# w13-input.net
KiCad netlist of a schematic drawn in EAGLE
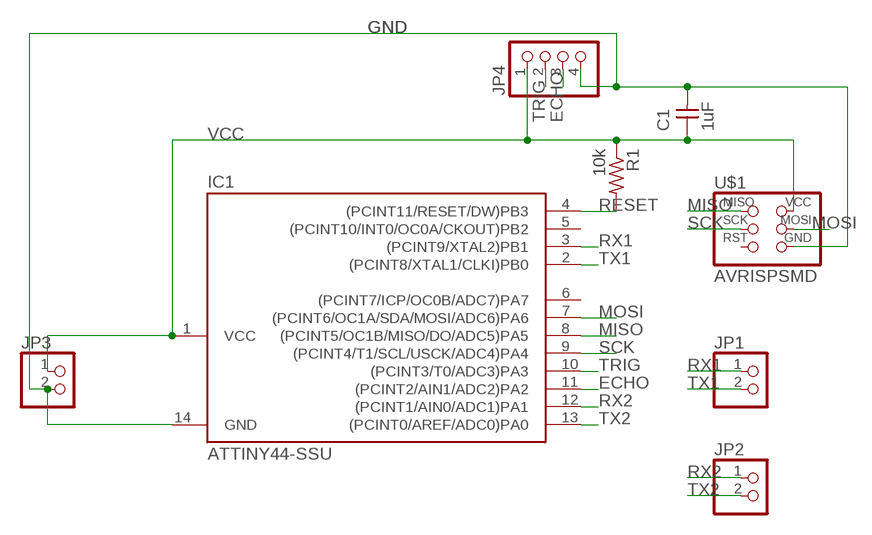
[diagram p0: schematic, sheet 1]

(export (version "E")
  (design (tool "Eeschema 10.0.6"))
  (components
    (comp (ref "C1")
      (value "1uF")
      (footprint "eagle-import:C1206FAB")
      (libsource (lib "eagle-import") (part "CAP-UNPOLARIZEDFAB"))
    )
    (comp (ref "IC1")
      (value "ATTINY44-SSU")
      (footprint "eagle-import:SOIC14")
      (libsource (lib "eagle-import") (part "ATTINY44-SSU"))
    )
    (comp (ref "JP1")
      (value "PINHD-1X2")
      (footprint "eagle-import:1X02")
      (libsource (lib "eagle-import") (part "PINHD-1X2"))
    )
    (comp (ref "JP2")
      (value "PINHD-1X2")
      (footprint "eagle-import:1X02")
      (libsource (lib "eagle-import") (part "PINHD-1X2"))
    )
    (comp (ref "JP3")
      (value "PINHD-1X2")
      (footprint "eagle-import:1X02")
      (libsource (lib "eagle-import") (part "PINHD-1X2"))
    )
    (comp (ref "JP4")
      (value "PINHD-1X4")
      (footprint "eagle-import:1X04")
      (libsource (lib "eagle-import") (part "PINHD-1X4"))
    )
    (comp (ref "R1")
      (value "10k")
      (footprint "eagle-import:R1206FAB")
      (libsource (lib "eagle-import") (part "RES-US1206FAB"))
    )
    (comp (ref "U$1")
      (value "AVRISPSMD")
      (footprint "eagle-import:2X03SMD")
      (libsource (lib "eagle-import") (part "AVRISPSMD"))
    )
  )
  (nets
    (net (code "1") (name "/ECHO") (class "Default")
      (node (ref "IC1") (pin "11") (pinfunction "(PCINT2/AIN1/ADC2)PA2_11") (pintype "bidirectional"))
      (node (ref "JP4") (pin "3") (pinfunction "3_3") (pintype "passive"))
    )
    (net (code "2") (name "/GND") (class "Default")
      (node (ref "C1") (pin "2") (pinfunction "2_2") (pintype "passive"))
      (node (ref "IC1") (pin "14") (pinfunction "GND_14") (pintype "power_in"))
      (node (ref "JP3") (pin "2") (pinfunction "2_2") (pintype "passive"))
      (node (ref "JP4") (pin "4") (pinfunction "4_4") (pintype "passive"))
      (node (ref "U$1") (pin "6") (pinfunction "GND_6") (pintype "passive"))
    )
    (net (code "3") (name "/MISO") (class "Default")
      (node (ref "IC1") (pin "8") (pinfunction "(PCINT5/OC1B/MISO/DO/ADC5)PA5_8") (pintype "bidirectional"))
      (node (ref "U$1") (pin "1") (pinfunction "MISO_1") (pintype "passive"))
    )
    (net (code "4") (name "/MOSI") (class "Default")
      (node (ref "IC1") (pin "7") (pinfunction "(PCINT6/OC1A/SDA/MOSI/ADC6)PA6_7") (pintype "bidirectional"))
      (node (ref "U$1") (pin "4") (pinfunction "MOSI_4") (pintype "passive"))
    )
    (net (code "5") (name "/RESET") (class "Default")
      (node (ref "IC1") (pin "4") (pinfunction "(PCINT11/RESET/DW)PB3_4") (pintype "bidirectional"))
      (node (ref "R1") (pin "2") (pinfunction "2_2") (pintype "passive"))
    )
    (net (code "6") (name "/RX1") (class "Default")
      (node (ref "IC1") (pin "3") (pinfunction "(PCINT9/XTAL2)PB1_3") (pintype "bidirectional"))
      (node (ref "JP1") (pin "1") (pinfunction "1_1") (pintype "passive"))
    )
    (net (code "7") (name "/RX2") (class "Default")
      (node (ref "IC1") (pin "12") (pinfunction "(PCINT1/AIN0/ADC1)PA1_12") (pintype "bidirectional"))
      (node (ref "JP2") (pin "1") (pinfunction "1_1") (pintype "passive"))
    )
    (net (code "8") (name "/SCK") (class "Default")
      (node (ref "IC1") (pin "9") (pinfunction "(PCINT4/T1/SCL/USCK/ADC4)PA4_9") (pintype "bidirectional"))
      (node (ref "U$1") (pin "3") (pinfunction "SCK_3") (pintype "passive"))
    )
    (net (code "9") (name "/TRIG") (class "Default")
      (node (ref "IC1") (pin "10") (pinfunction "(PCINT3/T0/ADC3)PA3_10") (pintype "bidirectional"))
      (node (ref "JP4") (pin "2") (pinfunction "2_2") (pintype "passive"))
    )
    (net (code "10") (name "/TX1") (class "Default")
      (node (ref "IC1") (pin "2") (pinfunction "(PCINT8/XTAL1/CLKI)PB0_2") (pintype "bidirectional"))
      (node (ref "JP1") (pin "2") (pinfunction "2_2") (pintype "passive"))
    )
    (net (code "11") (name "/TX2") (class "Default")
      (node (ref "IC1") (pin "13") (pinfunction "(PCINT0/AREF/ADC0)PA0_13") (pintype "bidirectional"))
      (node (ref "JP2") (pin "2") (pinfunction "2_2") (pintype "passive"))
    )
    (net (code "12") (name "/VCC") (class "Default")
      (node (ref "C1") (pin "1") (pinfunction "1_1") (pintype "passive"))
      (node (ref "IC1") (pin "1") (pinfunction "VCC_1") (pintype "power_in"))
      (node (ref "JP3") (pin "1") (pinfunction "1_1") (pintype "passive"))
      (node (ref "JP4") (pin "1") (pinfunction "1_1") (pintype "passive"))
      (node (ref "R1") (pin "1") (pinfunction "1_1") (pintype "passive"))
      (node (ref "U$1") (pin "2") (pinfunction "VCC_2") (pintype "passive"))
    )
    (net (code "13") (name "unconnected-(IC1-(PCINT7{slash}ICP{slash}OC0B{slash}ADC7)PA7-Pad6)") (class "Default")
      (node (ref "IC1") (pin "6") (pinfunction "(PCINT7/ICP/OC0B/ADC7)PA7_6") (pintype "bidirectional"))
    )
    (net (code "14") (name "unconnected-(IC1-(PCINT10{slash}INT0{slash}OC0A{slash}CKOUT)PB2-Pad5)") (class "Default")
      (node (ref "IC1") (pin "5") (pinfunction "(PCINT10/INT0/OC0A/CKOUT)PB2_5") (pintype "bidirectional"))
    )
    (net (code "15") (name "unconnected-(U$1-RST-Pad5)") (class "Default")
      (node (ref "U$1") (pin "5") (pinfunction "RST_5") (pintype "passive"))
    )
  )
)
